# Selectric.net
KiCad netlist of a schematic drawn in EAGLE
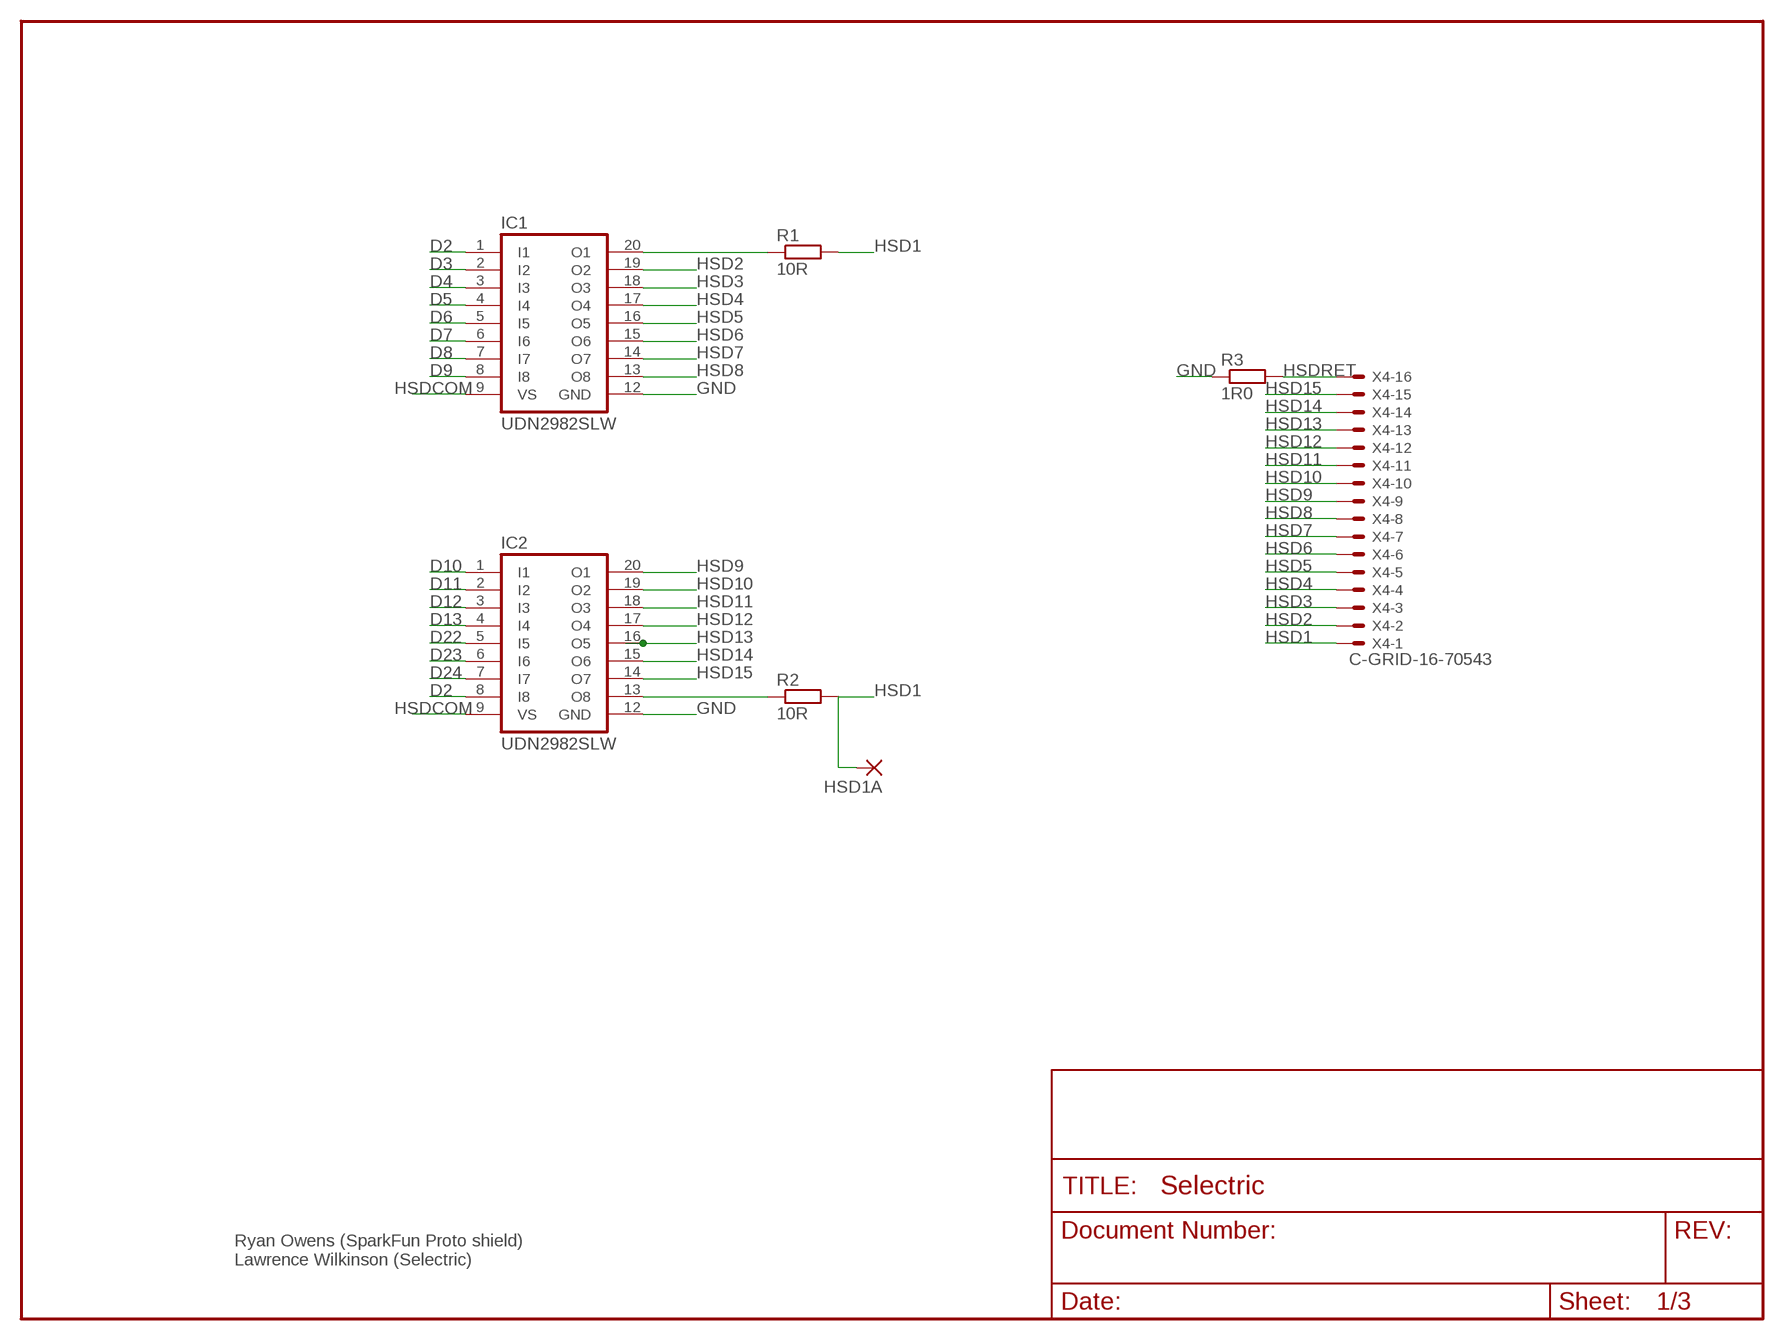
[diagram p0: schematic, sheet 1]
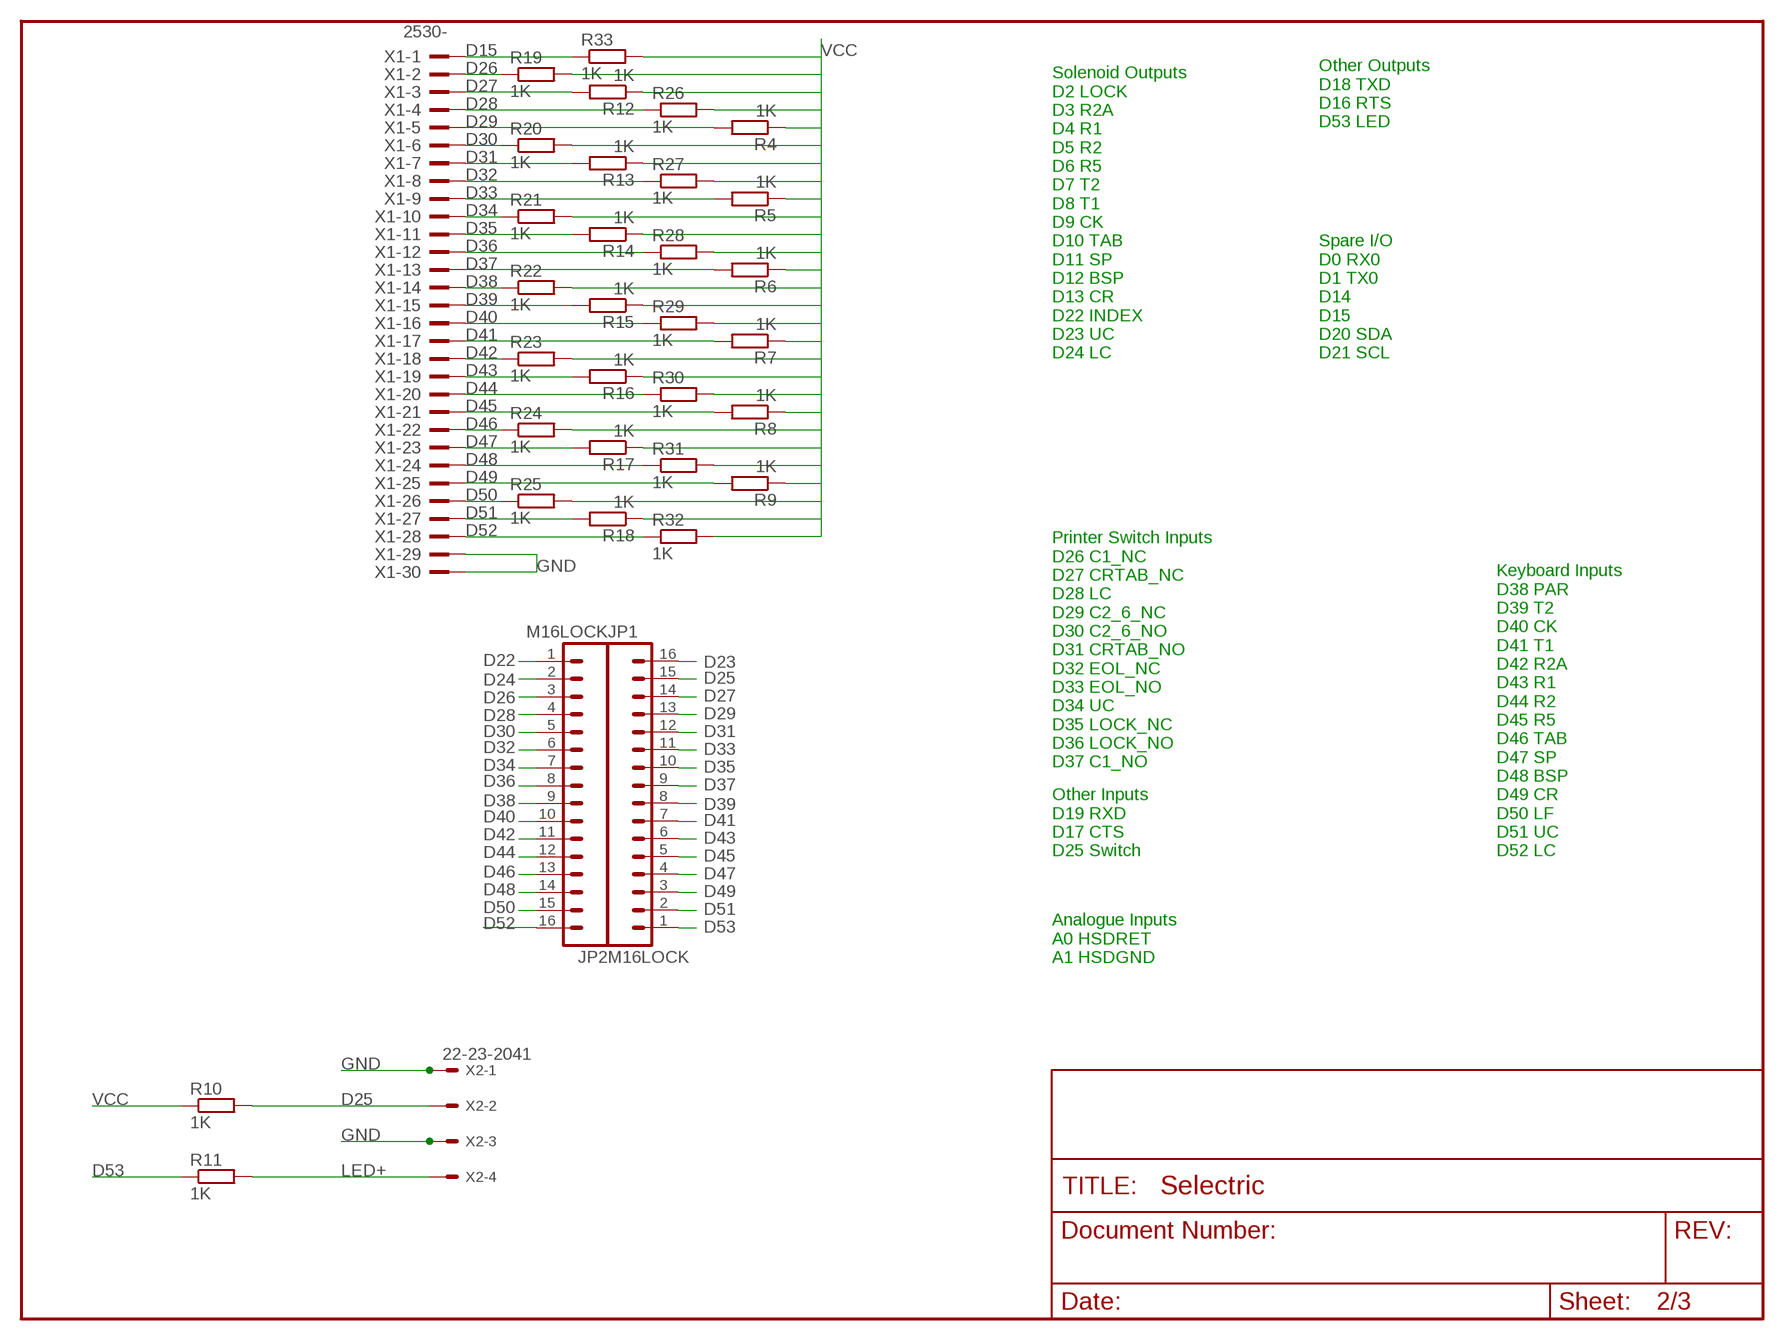
[diagram p1: schematic, sheet 2]
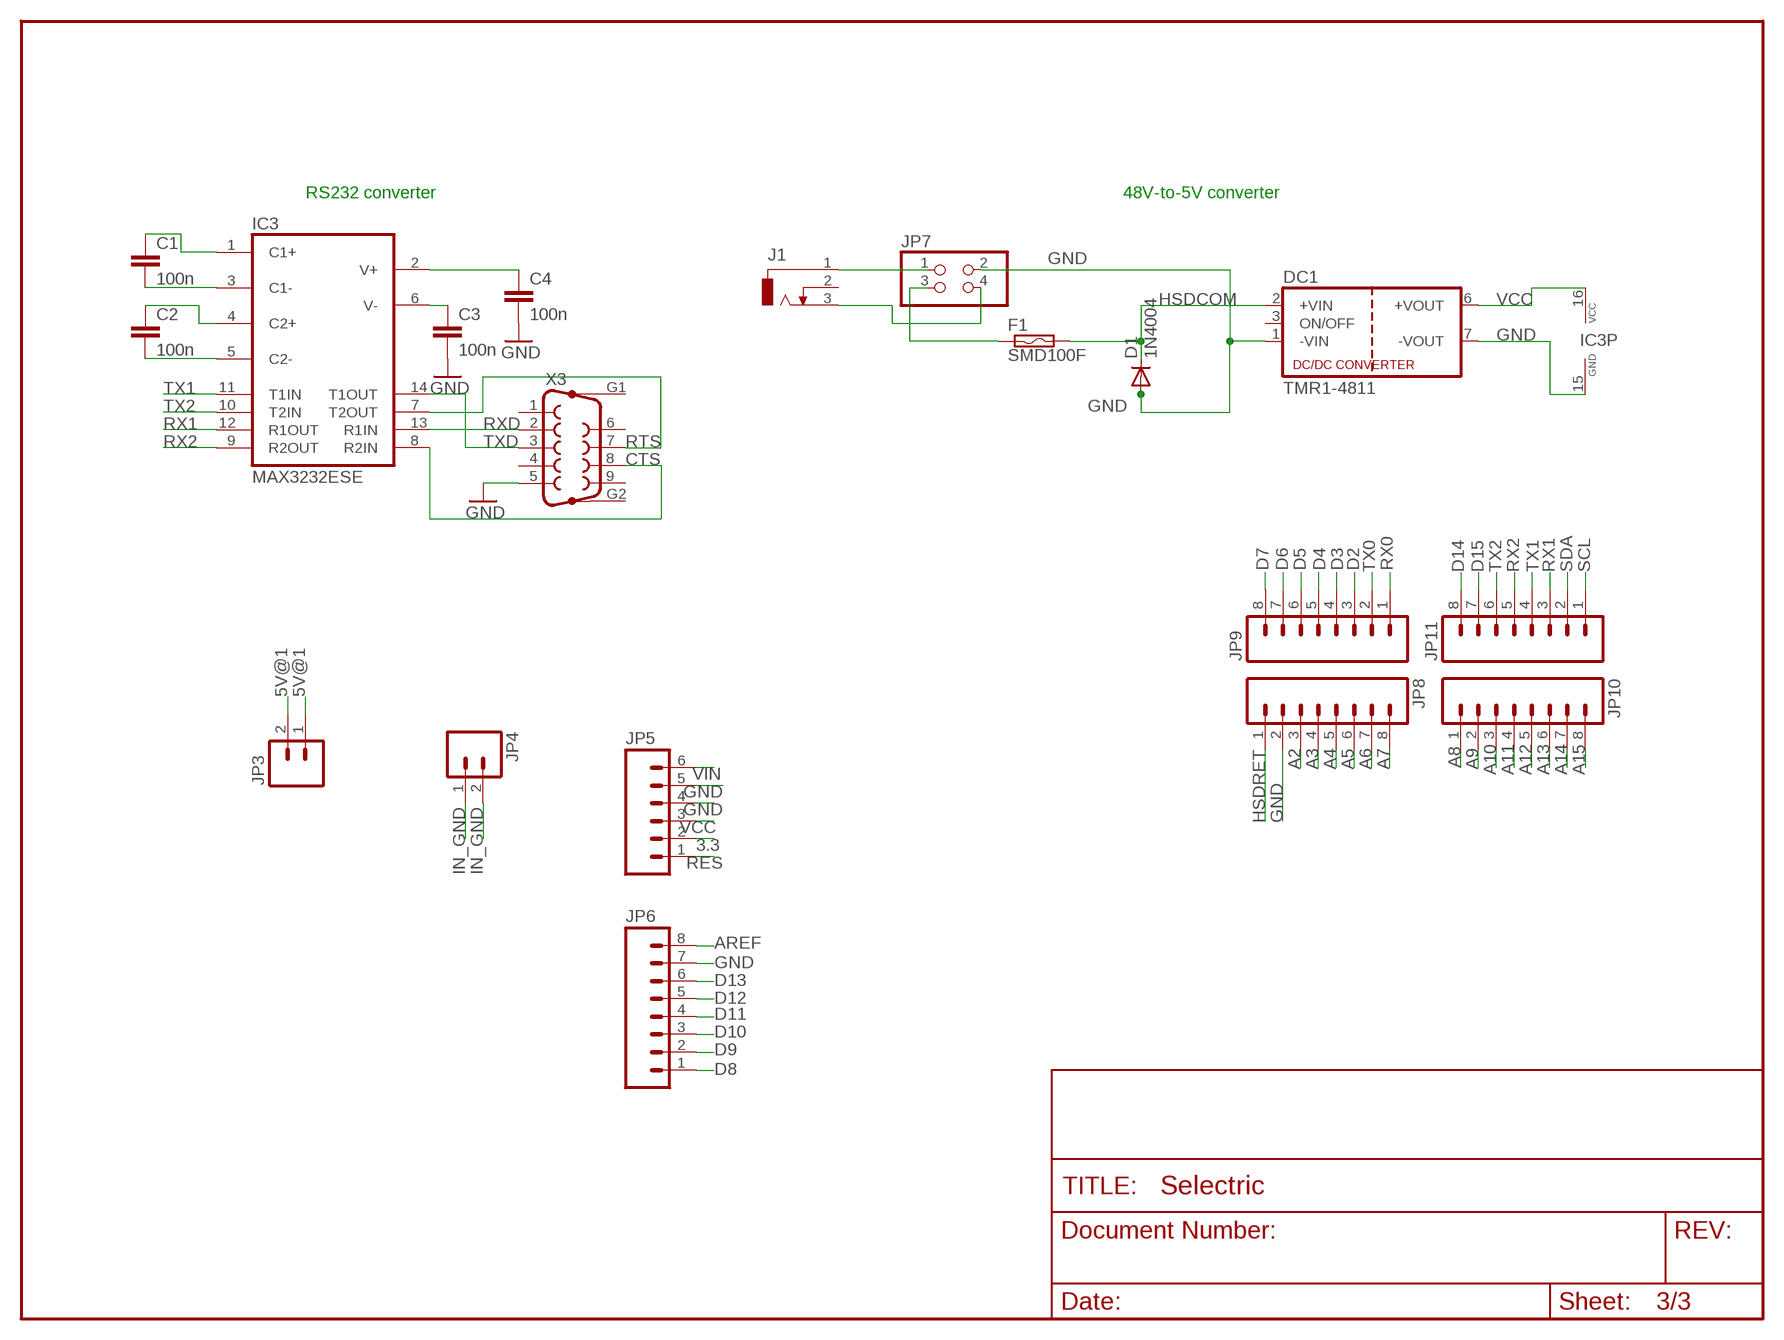
[diagram p2: schematic, sheet 3]

(export (version "E")
  (design (tool "Eeschema 10.0.6"))
  (components
    (comp (ref "HSD1A")
      (value "2,15/1,0")
      (footprint "eagle-import:2,15_1,0")
      (libsource (lib "eagle-import") (part "2,15/1,0"))
    )
    (comp (ref "IC1")
      (value "UDN2982SLW")
      (footprint "eagle-import:SO20W")
      (fields (field (name "MF") "Allegro"))
      (libsource (lib "eagle-import") (part "UDN298SLW2"))
    )
    (comp (ref "IC2")
      (value "UDN2982SLW")
      (footprint "eagle-import:SO20W")
      (fields (field (name "MF") "Allegro"))
      (libsource (lib "eagle-import") (part "UDN298SLW2"))
    )
    (comp (ref "R1")
      (value "10R")
      (footprint "eagle-import:M1206")
      (libsource (lib "eagle-import") (part "R-EU_M1206"))
    )
    (comp (ref "R2")
      (value "10R")
      (footprint "eagle-import:M1206")
      (libsource (lib "eagle-import") (part "R-EU_M1206"))
    )
    (comp (ref "R3")
      (value "1R0")
      (footprint "eagle-import:0922_22")
      (libsource (lib "eagle-import") (part "R-EU_0922/22"))
    )
    (comp (ref "X4")
      (value "C-GRID-16-70543")
      (footprint "eagle-import:70543-16")
      (libsource (lib "eagle-import") (part "C-GRID-16-70543"))
    )
    (comp (ref "JP1")
      (value "M16LOCK")
      (footprint "eagle-import:1X16_LOCK")
      (fields (field (name "MF") "WURTH") (field (name "MPN") "61301611121"))
      (libsource (lib "eagle-import") (part "M16LOCK"))
    )
    (comp (ref "JP2")
      (value "M16LOCK")
      (footprint "eagle-import:1X16_LOCK")
      (fields (field (name "MF") "WURTH") (field (name "MPN") "61301611121"))
      (libsource (lib "eagle-import") (part "M16LOCK"))
    )
    (comp (ref "R4")
      (value "1K")
      (footprint "eagle-import:M1206")
      (libsource (lib "eagle-import") (part "R-EU_M1206"))
    )
    (comp (ref "R5")
      (value "1K")
      (footprint "eagle-import:M1206")
      (libsource (lib "eagle-import") (part "R-EU_M1206"))
    )
    (comp (ref "R6")
      (value "1K")
      (footprint "eagle-import:M1206")
      (libsource (lib "eagle-import") (part "R-EU_M1206"))
    )
    (comp (ref "R7")
      (value "1K")
      (footprint "eagle-import:M1206")
      (libsource (lib "eagle-import") (part "R-EU_M1206"))
    )
    (comp (ref "R8")
      (value "1K")
      (footprint "eagle-import:M1206")
      (libsource (lib "eagle-import") (part "R-EU_M1206"))
    )
    (comp (ref "R9")
      (value "1K")
      (footprint "eagle-import:M1206")
      (libsource (lib "eagle-import") (part "R-EU_M1206"))
    )
    (comp (ref "R10")
      (value "1K")
      (footprint "eagle-import:M1206")
      (libsource (lib "eagle-import") (part "R-EU_M1206"))
    )
    (comp (ref "R11")
      (value "1K")
      (footprint "eagle-import:M1206")
      (libsource (lib "eagle-import") (part "R-EU_M1206"))
    )
    (comp (ref "R12")
      (value "1K")
      (footprint "eagle-import:M1206")
      (libsource (lib "eagle-import") (part "R-EU_M1206"))
    )
    (comp (ref "R13")
      (value "1K")
      (footprint "eagle-import:M1206")
      (libsource (lib "eagle-import") (part "R-EU_M1206"))
    )
    (comp (ref "R14")
      (value "1K")
      (footprint "eagle-import:M1206")
      (libsource (lib "eagle-import") (part "R-EU_M1206"))
    )
    (comp (ref "R15")
      (value "1K")
      (footprint "eagle-import:M1206")
      (libsource (lib "eagle-import") (part "R-EU_M1206"))
    )
    (comp (ref "R16")
      (value "1K")
      (footprint "eagle-import:M1206")
      (libsource (lib "eagle-import") (part "R-EU_M1206"))
    )
    (comp (ref "R17")
      (value "1K")
      (footprint "eagle-import:M1206")
      (libsource (lib "eagle-import") (part "R-EU_M1206"))
    )
    (comp (ref "R18")
      (value "1K")
      (footprint "eagle-import:M1206")
      (libsource (lib "eagle-import") (part "R-EU_M1206"))
    )
    (comp (ref "R19")
      (value "1K")
      (footprint "eagle-import:M1206")
      (libsource (lib "eagle-import") (part "R-EU_M1206"))
    )
    (comp (ref "R20")
      (value "1K")
      (footprint "eagle-import:M1206")
      (libsource (lib "eagle-import") (part "R-EU_M1206"))
    )
    (comp (ref "R21")
      (value "1K")
      (footprint "eagle-import:M1206")
      (libsource (lib "eagle-import") (part "R-EU_M1206"))
    )
    (comp (ref "R22")
      (value "1K")
      (footprint "eagle-import:M1206")
      (libsource (lib "eagle-import") (part "R-EU_M1206"))
    )
    (comp (ref "R23")
      (value "1K")
      (footprint "eagle-import:M1206")
      (libsource (lib "eagle-import") (part "R-EU_M1206"))
    )
    (comp (ref "R24")
      (value "1K")
      (footprint "eagle-import:M1206")
      (libsource (lib "eagle-import") (part "R-EU_M1206"))
    )
    (comp (ref "R25")
      (value "1K")
      (footprint "eagle-import:M1206")
      (libsource (lib "eagle-import") (part "R-EU_M1206"))
    )
    (comp (ref "R26")
      (value "1K")
      (footprint "eagle-import:M1206")
      (libsource (lib "eagle-import") (part "R-EU_M1206"))
    )
    (comp (ref "R27")
      (value "1K")
      (footprint "eagle-import:M1206")
      (libsource (lib "eagle-import") (part "R-EU_M1206"))
    )
    (comp (ref "R28")
      (value "1K")
      (footprint "eagle-import:M1206")
      (libsource (lib "eagle-import") (part "R-EU_M1206"))
    )
    (comp (ref "R29")
      (value "1K")
      (footprint "eagle-import:M1206")
      (libsource (lib "eagle-import") (part "R-EU_M1206"))
    )
    (comp (ref "R30")
      (value "1K")
      (footprint "eagle-import:M1206")
      (libsource (lib "eagle-import") (part "R-EU_M1206"))
    )
    (comp (ref "R31")
      (value "1K")
      (footprint "eagle-import:M1206")
      (libsource (lib "eagle-import") (part "R-EU_M1206"))
    )
    (comp (ref "R32")
      (value "1K")
      (footprint "eagle-import:M1206")
      (libsource (lib "eagle-import") (part "R-EU_M1206"))
    )
    (comp (ref "R33")
      (value "1K")
      (footprint "eagle-import:M1206")
      (libsource (lib "eagle-import") (part "R-EU_M1206"))
    )
    (comp (ref "X1")
      (value "2530-")
      (footprint "eagle-import:PAK100_2500-30")
      (fields (field (name "MF") "3M") (field (name "MPN") "PAK100/2500-30"))
      (libsource (lib "eagle-import") (part "2530-"))
    )
    (comp (ref "X2")
      (value "22-23-2041")
      (footprint "eagle-import:22-23-2041")
      (fields
        (field (name "MF") "MOLEX")
        (field (name "MF_1") "TE CONNECTIVITY")
        (field (name "MPN") "280371-2")
      )
      (libsource (lib "eagle-import") (part "22-23-2041"))
    )
    (comp (ref "C1")
      (value "100n")
      (footprint "eagle-import:C0603")
      (libsource (lib "eagle-import") (part "C-EUC0603"))
    )
    (comp (ref "C2")
      (value "100n")
      (footprint "eagle-import:C0603")
      (libsource (lib "eagle-import") (part "C-EUC0603"))
    )
    (comp (ref "C3")
      (value "100n")
      (footprint "eagle-import:C0603")
      (libsource (lib "eagle-import") (part "C-EUC0603"))
    )
    (comp (ref "C4")
      (value "100n")
      (footprint "eagle-import:C0603")
      (libsource (lib "eagle-import") (part "C-EUC0603"))
    )
    (comp (ref "D1")
      (value "1N4004")
      (footprint "eagle-import:DO41-10")
      (libsource (lib "eagle-import") (part "1N4004"))
    )
    (comp (ref "DC1")
      (value "TMR1-4811")
      (footprint "eagle-import:TRACO_SIP-8")
      (fields (field (name "MF") "TRACO"))
      (libsource (lib "eagle-import") (part "TMR1-4811"))
    )
    (comp (ref "F1")
      (value "SMD100F")
      (footprint "eagle-import:SMD050F")
      (fields (field (name "MF") "Schurter") (field (name "MPN") "3404.0009.11"))
      (libsource (lib "eagle-import") (part "SMDF100"))
    )
    (comp (ref "IC3")
      (value "MAX3232ESE")
      (footprint "eagle-import:SO16")
      (fields (field (name "MF") "MAXIM") (field (name "MPN") "MAX3232CSE"))
      (libsource (lib "eagle-import") (part "MAX3232SEE"))
    )
    (comp (ref "J1")
      (value "DCJ0303")
      (footprint "eagle-import:DCJ0303")
      (libsource (lib "eagle-import") (part "DCJ0303"))
    )
    (comp (ref "JP3")
      (value "M02LOCK")
      (footprint "eagle-import:1X02_LOCK")
      (libsource (lib "eagle-import") (part "M02LOCK"))
    )
    (comp (ref "JP4")
      (value "M02LOCK")
      (footprint "eagle-import:1X02_LOCK")
      (libsource (lib "eagle-import") (part "M02LOCK"))
    )
    (comp (ref "JP5")
      (value "M06LOCK")
      (footprint "eagle-import:1X06_LOCK")
      (fields (field (name "MF") "TE CONNECTIVITY") (field (name "MPN") "826629-6"))
      (libsource (lib "eagle-import") (part "M06LOCK"))
    )
    (comp (ref "JP6")
      (value "M08LOCK")
      (footprint "eagle-import:1X08_LOCK")
      (fields (field (name "MF") "TE CONNECTIVITY") (field (name "MPN") "826629-8"))
      (libsource (lib "eagle-import") (part "M08LOCK"))
    )
    (comp (ref "JP7")
      (value "PINHD-2X2")
      (footprint "eagle-import:2X02")
      (fields (field (name "MF") "TE CONNECTIVITY") (field (name "MPN") "826632-2"))
      (libsource (lib "eagle-import") (part "PINHD-2X2"))
    )
    (comp (ref "JP8")
      (value "M08LOCK")
      (footprint "eagle-import:1X08_LOCK")
      (fields (field (name "MF") "TE CONNECTIVITY") (field (name "MPN") "826629-8"))
      (libsource (lib "eagle-import") (part "M08LOCK"))
    )
    (comp (ref "JP9")
      (value "M08LOCK")
      (footprint "eagle-import:1X08_LOCK")
      (fields (field (name "MF") "TE CONNECTIVITY") (field (name "MPN") "826629-8"))
      (libsource (lib "eagle-import") (part "M08LOCK"))
    )
    (comp (ref "JP10")
      (value "M08LOCK")
      (footprint "eagle-import:1X08_LOCK")
      (fields (field (name "MF") "TE CONNECTIVITY") (field (name "MPN") "826629-8"))
      (libsource (lib "eagle-import") (part "M08LOCK"))
    )
    (comp (ref "JP11")
      (value "M08LOCK")
      (footprint "eagle-import:1X08_LOCK")
      (fields (field (name "MF") "TE CONNECTIVITY") (field (name "MPN") "826629-8"))
      (libsource (lib "eagle-import") (part "M08LOCK"))
    )
    (comp (ref "X3")
      (value "F09HP")
      (footprint "eagle-import:F09HP")
      (fields (field (name "MF") "Amphenol") (field (name "MPN") "FCE17-E09PA-490"))
      (libsource (lib "eagle-import") (part "F09HP"))
    )
  )
  (nets
    (net (code "1") (name "3.3") (class "Default")
      (node (ref "JP5") (pin "2") (pinfunction "2_2") (pintype "passive"))
    )
    (net (code "2") (name "5V@1") (class "Default")
      (node (ref "JP3") (pin "1") (pinfunction "1_1") (pintype "passive"))
      (node (ref "JP3") (pin "2") (pinfunction "2_2") (pintype "passive"))
    )
    (net (code "3") (name "A2") (class "Default")
      (node (ref "JP8") (pin "3") (pinfunction "3_3") (pintype "passive"))
    )
    (net (code "4") (name "A3") (class "Default")
      (node (ref "JP8") (pin "4") (pinfunction "4_4") (pintype "passive"))
    )
    (net (code "5") (name "A4") (class "Default")
      (node (ref "JP8") (pin "5") (pinfunction "5_5") (pintype "passive"))
    )
    (net (code "6") (name "A5") (class "Default")
      (node (ref "JP8") (pin "6") (pinfunction "6_6") (pintype "passive"))
    )
    (net (code "7") (name "A6") (class "Default")
      (node (ref "JP8") (pin "7") (pinfunction "7_7") (pintype "passive"))
    )
    (net (code "8") (name "A7") (class "Default")
      (node (ref "JP8") (pin "8") (pinfunction "8_8") (pintype "passive"))
    )
    (net (code "9") (name "A8") (class "Default")
      (node (ref "JP10") (pin "1") (pinfunction "1_1") (pintype "passive"))
    )
    (net (code "10") (name "A9") (class "Default")
      (node (ref "JP10") (pin "2") (pinfunction "2_2") (pintype "passive"))
    )
    (net (code "11") (name "A10") (class "Default")
      (node (ref "JP10") (pin "3") (pinfunction "3_3") (pintype "passive"))
    )
    (net (code "12") (name "A11") (class "Default")
      (node (ref "JP10") (pin "4") (pinfunction "4_4") (pintype "passive"))
    )
    (net (code "13") (name "A12") (class "Default")
      (node (ref "JP10") (pin "5") (pinfunction "5_5") (pintype "passive"))
    )
    (net (code "14") (name "A13") (class "Default")
      (node (ref "JP10") (pin "6") (pinfunction "6_6") (pintype "passive"))
    )
    (net (code "15") (name "A14") (class "Default")
      (node (ref "JP10") (pin "7") (pinfunction "7_7") (pintype "passive"))
    )
    (net (code "16") (name "A15") (class "Default")
      (node (ref "JP10") (pin "8") (pinfunction "8_8") (pintype "passive"))
    )
    (net (code "17") (name "AREF") (class "Default")
      (node (ref "JP6") (pin "8") (pinfunction "8_8") (pintype "passive"))
    )
    (net (code "18") (name "CTS") (class "Default")
      (node (ref "IC3") (pin "8") (pinfunction "R2IN_8") (pintype "input"))
      (node (ref "X3") (pin "8") (pinfunction "8_8") (pintype "passive"))
    )
    (net (code "19") (name "D2") (class "Default")
      (node (ref "IC1") (pin "1") (pinfunction "I1_1") (pintype "input"))
      (node (ref "IC2") (pin "8") (pinfunction "I8_8") (pintype "input"))
      (node (ref "JP9") (pin "3") (pinfunction "3_3") (pintype "passive"))
    )
    (net (code "20") (name "D3") (class "Default")
      (node (ref "IC1") (pin "2") (pinfunction "I2_2") (pintype "input"))
      (node (ref "JP9") (pin "4") (pinfunction "4_4") (pintype "passive"))
    )
    (net (code "21") (name "D4") (class "Default")
      (node (ref "IC1") (pin "3") (pinfunction "I3_3") (pintype "input"))
      (node (ref "JP9") (pin "5") (pinfunction "5_5") (pintype "passive"))
    )
    (net (code "22") (name "D5") (class "Default")
      (node (ref "IC1") (pin "4") (pinfunction "I4_4") (pintype "input"))
      (node (ref "JP9") (pin "6") (pinfunction "6_6") (pintype "passive"))
    )
    (net (code "23") (name "D6") (class "Default")
      (node (ref "IC1") (pin "5") (pinfunction "I5_5") (pintype "input"))
      (node (ref "JP9") (pin "7") (pinfunction "7_7") (pintype "passive"))
    )
    (net (code "24") (name "D7") (class "Default")
      (node (ref "IC1") (pin "6") (pinfunction "I6_6") (pintype "input"))
      (node (ref "JP9") (pin "8") (pinfunction "8_8") (pintype "passive"))
    )
    (net (code "25") (name "D8") (class "Default")
      (node (ref "IC1") (pin "7") (pinfunction "I7_7") (pintype "input"))
      (node (ref "JP6") (pin "1") (pinfunction "1_1") (pintype "passive"))
    )
    (net (code "26") (name "D9") (class "Default")
      (node (ref "IC1") (pin "8") (pinfunction "I8_8") (pintype "input"))
      (node (ref "JP6") (pin "2") (pinfunction "2_2") (pintype "passive"))
    )
    (net (code "27") (name "D10") (class "Default")
      (node (ref "IC2") (pin "1") (pinfunction "I1_1") (pintype "input"))
      (node (ref "JP6") (pin "3") (pinfunction "3_3") (pintype "passive"))
    )
    (net (code "28") (name "D11") (class "Default")
      (node (ref "IC2") (pin "2") (pinfunction "I2_2") (pintype "input"))
      (node (ref "JP6") (pin "4") (pinfunction "4_4") (pintype "passive"))
    )
    (net (code "29") (name "D12") (class "Default")
      (node (ref "IC2") (pin "3") (pinfunction "I3_3") (pintype "input"))
      (node (ref "JP6") (pin "5") (pinfunction "5_5") (pintype "passive"))
    )
    (net (code "30") (name "D13") (class "Default")
      (node (ref "IC2") (pin "4") (pinfunction "I4_4") (pintype "input"))
      (node (ref "JP6") (pin "6") (pinfunction "6_6") (pintype "passive"))
    )
    (net (code "31") (name "D14") (class "Default")
      (node (ref "JP11") (pin "8") (pinfunction "8_8") (pintype "passive"))
    )
    (net (code "32") (name "D15") (class "Default")
      (node (ref "JP11") (pin "7") (pinfunction "7_7") (pintype "passive"))
      (node (ref "R33") (pin "1") (pinfunction "1_1") (pintype "passive"))
      (node (ref "X1") (pin "1") (pinfunction "KL_1") (pintype "passive"))
    )
    (net (code "33") (name "D22") (class "Default")
      (node (ref "IC2") (pin "5") (pinfunction "I5_5") (pintype "input"))
      (node (ref "JP2") (pin "1") (pinfunction "1_1") (pintype "passive"))
    )
    (net (code "34") (name "D23") (class "Default")
      (node (ref "IC2") (pin "6") (pinfunction "I6_6") (pintype "input"))
      (node (ref "JP1") (pin "16") (pinfunction "16_16") (pintype "passive"))
    )
    (net (code "35") (name "D24") (class "Default")
      (node (ref "IC2") (pin "7") (pinfunction "I7_7") (pintype "input"))
      (node (ref "JP2") (pin "2") (pinfunction "2_2") (pintype "passive"))
    )
    (net (code "36") (name "D25") (class "Default")
      (node (ref "JP1") (pin "15") (pinfunction "15_15") (pintype "passive"))
      (node (ref "R10") (pin "2") (pinfunction "2_2") (pintype "passive"))
      (node (ref "X2") (pin "2") (pinfunction "S_2") (pintype "passive"))
    )
    (net (code "37") (name "D26") (class "Default")
      (node (ref "JP2") (pin "3") (pinfunction "3_3") (pintype "passive"))
      (node (ref "R19") (pin "1") (pinfunction "1_1") (pintype "passive"))
      (node (ref "X1") (pin "2") (pinfunction "KL_2") (pintype "passive"))
    )
    (net (code "38") (name "D27") (class "Default")
      (node (ref "JP1") (pin "14") (pinfunction "14_14") (pintype "passive"))
      (node (ref "R12") (pin "2") (pinfunction "2_2") (pintype "passive"))
      (node (ref "X1") (pin "3") (pinfunction "KL_3") (pintype "passive"))
    )
    (net (code "39") (name "D28") (class "Default")
      (node (ref "JP2") (pin "4") (pinfunction "4_4") (pintype "passive"))
      (node (ref "R26") (pin "1") (pinfunction "1_1") (pintype "passive"))
      (node (ref "X1") (pin "4") (pinfunction "KL_4") (pintype "passive"))
    )
    (net (code "40") (name "D29") (class "Default")
      (node (ref "JP1") (pin "13") (pinfunction "13_13") (pintype "passive"))
      (node (ref "R4") (pin "2") (pinfunction "2_2") (pintype "passive"))
      (node (ref "X1") (pin "5") (pinfunction "KL_5") (pintype "passive"))
    )
    (net (code "41") (name "D30") (class "Default")
      (node (ref "JP2") (pin "5") (pinfunction "5_5") (pintype "passive"))
      (node (ref "R20") (pin "1") (pinfunction "1_1") (pintype "passive"))
      (node (ref "X1") (pin "6") (pinfunction "KL_6") (pintype "passive"))
    )
    (net (code "42") (name "D31") (class "Default")
      (node (ref "JP1") (pin "12") (pinfunction "12_12") (pintype "passive"))
      (node (ref "R13") (pin "2") (pinfunction "2_2") (pintype "passive"))
      (node (ref "X1") (pin "7") (pinfunction "KL_7") (pintype "passive"))
    )
    (net (code "43") (name "D32") (class "Default")
      (node (ref "JP2") (pin "6") (pinfunction "6_6") (pintype "passive"))
      (node (ref "R27") (pin "1") (pinfunction "1_1") (pintype "passive"))
      (node (ref "X1") (pin "8") (pinfunction "KL_8") (pintype "passive"))
    )
    (net (code "44") (name "D33") (class "Default")
      (node (ref "JP1") (pin "11") (pinfunction "11_11") (pintype "passive"))
      (node (ref "R5") (pin "2") (pinfunction "2_2") (pintype "passive"))
      (node (ref "X1") (pin "9") (pinfunction "KL_9") (pintype "passive"))
    )
    (net (code "45") (name "D34") (class "Default")
      (node (ref "JP2") (pin "7") (pinfunction "7_7") (pintype "passive"))
      (node (ref "R21") (pin "1") (pinfunction "1_1") (pintype "passive"))
      (node (ref "X1") (pin "10") (pinfunction "KL_10") (pintype "passive"))
    )
    (net (code "46") (name "D35") (class "Default")
      (node (ref "JP1") (pin "10") (pinfunction "10_10") (pintype "passive"))
      (node (ref "R14") (pin "2") (pinfunction "2_2") (pintype "passive"))
      (node (ref "X1") (pin "11") (pinfunction "KL_11") (pintype "passive"))
    )
    (net (code "47") (name "D36") (class "Default")
      (node (ref "JP2") (pin "8") (pinfunction "8_8") (pintype "passive"))
      (node (ref "R28") (pin "1") (pinfunction "1_1") (pintype "passive"))
      (node (ref "X1") (pin "12") (pinfunction "KL_12") (pintype "passive"))
    )
    (net (code "48") (name "D37") (class "Default")
      (node (ref "JP1") (pin "9") (pinfunction "9_9") (pintype "passive"))
      (node (ref "R6") (pin "2") (pinfunction "2_2") (pintype "passive"))
      (node (ref "X1") (pin "13") (pinfunction "KL_13") (pintype "passive"))
    )
    (net (code "49") (name "D38") (class "Default")
      (node (ref "JP2") (pin "9") (pinfunction "9_9") (pintype "passive"))
      (node (ref "R22") (pin "1") (pinfunction "1_1") (pintype "passive"))
      (node (ref "X1") (pin "14") (pinfunction "KL_14") (pintype "passive"))
    )
    (net (code "50") (name "D39") (class "Default")
      (node (ref "JP1") (pin "8") (pinfunction "8_8") (pintype "passive"))
      (node (ref "R15") (pin "2") (pinfunction "2_2") (pintype "passive"))
      (node (ref "X1") (pin "15") (pinfunction "KL_15") (pintype "passive"))
    )
    (net (code "51") (name "D40") (class "Default")
      (node (ref "JP2") (pin "10") (pinfunction "10_10") (pintype "passive"))
      (node (ref "R29") (pin "1") (pinfunction "1_1") (pintype "passive"))
      (node (ref "X1") (pin "16") (pinfunction "KL_16") (pintype "passive"))
    )
    (net (code "52") (name "D41") (class "Default")
      (node (ref "JP1") (pin "7") (pinfunction "7_7") (pintype "passive"))
      (node (ref "R7") (pin "2") (pinfunction "2_2") (pintype "passive"))
      (node (ref "X1") (pin "17") (pinfunction "KL_17") (pintype "passive"))
    )
    (net (code "53") (name "D42") (class "Default")
      (node (ref "JP2") (pin "11") (pinfunction "11_11") (pintype "passive"))
      (node (ref "R23") (pin "1") (pinfunction "1_1") (pintype "passive"))
      (node (ref "X1") (pin "18") (pinfunction "KL_18") (pintype "passive"))
    )
    (net (code "54") (name "D43") (class "Default")
      (node (ref "JP1") (pin "6") (pinfunction "6_6") (pintype "passive"))
      (node (ref "R16") (pin "2") (pinfunction "2_2") (pintype "passive"))
      (node (ref "X1") (pin "19") (pinfunction "KL_19") (pintype "passive"))
    )
    (net (code "55") (name "D44") (class "Default")
      (node (ref "JP2") (pin "12") (pinfunction "12_12") (pintype "passive"))
      (node (ref "R30") (pin "1") (pinfunction "1_1") (pintype "passive"))
      (node (ref "X1") (pin "20") (pinfunction "KL_20") (pintype "passive"))
    )
    (net (code "56") (name "D45") (class "Default")
      (node (ref "JP1") (pin "5") (pinfunction "5_5") (pintype "passive"))
      (node (ref "R8") (pin "2") (pinfunction "2_2") (pintype "passive"))
      (node (ref "X1") (pin "21") (pinfunction "KL_21") (pintype "passive"))
    )
    (net (code "57") (name "D46") (class "Default")
      (node (ref "JP2") (pin "13") (pinfunction "13_13") (pintype "passive"))
      (node (ref "R24") (pin "1") (pinfunction "1_1") (pintype "passive"))
      (node (ref "X1") (pin "22") (pinfunction "KL_22") (pintype "passive"))
    )
    (net (code "58") (name "D47") (class "Default")
      (node (ref "JP1") (pin "4") (pinfunction "4_4") (pintype "passive"))
      (node (ref "R17") (pin "2") (pinfunction "2_2") (pintype "passive"))
      (node (ref "X1") (pin "23") (pinfunction "KL_23") (pintype "passive"))
    )
    (net (code "59") (name "D48") (class "Default")
      (node (ref "JP2") (pin "14") (pinfunction "14_14") (pintype "passive"))
      (node (ref "R31") (pin "1") (pinfunction "1_1") (pintype "passive"))
      (node (ref "X1") (pin "24") (pinfunction "KL_24") (pintype "passive"))
    )
    (net (code "60") (name "D49") (class "Default")
      (node (ref "JP1") (pin "3") (pinfunction "3_3") (pintype "passive"))
      (node (ref "R9") (pin "2") (pinfunction "2_2") (pintype "passive"))
      (node (ref "X1") (pin "25") (pinfunction "KL_25") (pintype "passive"))
    )
    (net (code "61") (name "D50") (class "Default")
      (node (ref "JP2") (pin "15") (pinfunction "15_15") (pintype "passive"))
      (node (ref "R25") (pin "1") (pinfunction "1_1") (pintype "passive"))
      (node (ref "X1") (pin "26") (pinfunction "KL_26") (pintype "passive"))
    )
    (net (code "62") (name "D51") (class "Default")
      (node (ref "JP1") (pin "2") (pinfunction "2_2") (pintype "passive"))
      (node (ref "R18") (pin "2") (pinfunction "2_2") (pintype "passive"))
      (node (ref "X1") (pin "27") (pinfunction "KL_27") (pintype "passive"))
    )
    (net (code "63") (name "D52") (class "Default")
      (node (ref "JP2") (pin "16") (pinfunction "16_16") (pintype "passive"))
      (node (ref "R32") (pin "1") (pinfunction "1_1") (pintype "passive"))
      (node (ref "X1") (pin "28") (pinfunction "KL_28") (pintype "passive"))
    )
    (net (code "64") (name "D53") (class "Default")
      (node (ref "JP1") (pin "1") (pinfunction "1_1") (pintype "passive"))
      (node (ref "R11") (pin "1") (pinfunction "1_1") (pintype "passive"))
    )
    (net (code "65") (name "GND") (class "Default")
      (node (ref "C3") (pin "2") (pinfunction "2_2") (pintype "passive"))
      (node (ref "C4") (pin "2") (pinfunction "2_2") (pintype "passive"))
      (node (ref "D1") (pin "A") (pinfunction "A_A") (pintype "passive"))
      (node (ref "DC1") (pin "1") (pinfunction "-VIN_1") (pintype "passive"))
      (node (ref "DC1") (pin "7") (pinfunction "-VOUT_7") (pintype "passive"))
      (node (ref "IC1") (pin "12") (pinfunction "GND_12") (pintype "power_in"))
      (node (ref "IC2") (pin "12") (pinfunction "GND_12") (pintype "power_in"))
      (node (ref "IC3") (pin "15") (pinfunction "GND_15") (pintype "power_in"))
      (node (ref "JP5") (pin "4") (pinfunction "4_4") (pintype "passive"))
      (node (ref "JP5") (pin "5") (pinfunction "5_5") (pintype "passive"))
      (node (ref "JP6") (pin "7") (pinfunction "7_7") (pintype "passive"))
      (node (ref "JP7") (pin "2") (pinfunction "2_2") (pintype "passive"))
      (node (ref "JP8") (pin "2") (pinfunction "2_2") (pintype "passive"))
      (node (ref "R3") (pin "1") (pinfunction "1_1") (pintype "passive"))
      (node (ref "X1") (pin "29") (pinfunction "KL_29") (pintype "passive"))
      (node (ref "X1") (pin "30") (pinfunction "KL_30") (pintype "passive"))
      (node (ref "X2") (pin "1") (pinfunction "S_1") (pintype "passive"))
      (node (ref "X2") (pin "3") (pinfunction "S_3") (pintype "passive"))
      (node (ref "X3") (pin "5") (pinfunction "5_5") (pintype "passive"))
    )
    (net (code "66") (name "HSD1") (class "Default")
      (node (ref "HSD1A") (pin "1") (pinfunction "P_1") (pintype "passive"))
      (node (ref "R1") (pin "2") (pinfunction "2_2") (pintype "passive"))
      (node (ref "R2") (pin "2") (pinfunction "2_2") (pintype "passive"))
      (node (ref "X4") (pin "1") (pinfunction "S_1") (pintype "passive"))
    )
    (net (code "67") (name "HSD2") (class "Default")
      (node (ref "IC1") (pin "19") (pinfunction "O2_19") (pintype "open_collector"))
      (node (ref "X4") (pin "2") (pinfunction "S_2") (pintype "passive"))
    )
    (net (code "68") (name "HSD3") (class "Default")
      (node (ref "IC1") (pin "18") (pinfunction "O3_18") (pintype "open_collector"))
      (node (ref "X4") (pin "3") (pinfunction "S_3") (pintype "passive"))
    )
    (net (code "69") (name "HSD4") (class "Default")
      (node (ref "IC1") (pin "17") (pinfunction "O4_17") (pintype "open_collector"))
      (node (ref "X4") (pin "4") (pinfunction "S_4") (pintype "passive"))
    )
    (net (code "70") (name "HSD5") (class "Default")
      (node (ref "IC1") (pin "16") (pinfunction "O5_16") (pintype "open_collector"))
      (node (ref "X4") (pin "5") (pinfunction "S_5") (pintype "passive"))
    )
    (net (code "71") (name "HSD6") (class "Default")
      (node (ref "IC1") (pin "15") (pinfunction "O6_15") (pintype "open_collector"))
      (node (ref "X4") (pin "6") (pinfunction "S_6") (pintype "passive"))
    )
    (net (code "72") (name "HSD7") (class "Default")
      (node (ref "IC1") (pin "14") (pinfunction "O7_14") (pintype "open_collector"))
      (node (ref "X4") (pin "7") (pinfunction "S_7") (pintype "passive"))
    )
    (net (code "73") (name "HSD8") (class "Default")
      (node (ref "IC1") (pin "13") (pinfunction "O8_13") (pintype "open_collector"))
      (node (ref "X4") (pin "8") (pinfunction "S_8") (pintype "passive"))
    )
    (net (code "74") (name "HSD9") (class "Default")
      (node (ref "IC2") (pin "20") (pinfunction "O1_20") (pintype "open_collector"))
      (node (ref "X4") (pin "9") (pinfunction "S_9") (pintype "passive"))
    )
    (net (code "75") (name "HSD10") (class "Default")
      (node (ref "IC2") (pin "19") (pinfunction "O2_19") (pintype "open_collector"))
      (node (ref "X4") (pin "10") (pinfunction "S_10") (pintype "passive"))
    )
    (net (code "76") (name "HSD11") (class "Default")
      (node (ref "IC2") (pin "18") (pinfunction "O3_18") (pintype "open_collector"))
      (node (ref "X4") (pin "11") (pinfunction "S_11") (pintype "passive"))
    )
    (net (code "77") (name "HSD12") (class "Default")
      (node (ref "IC2") (pin "17") (pinfunction "O4_17") (pintype "open_collector"))
      (node (ref "X4") (pin "12") (pinfunction "S_12") (pintype "passive"))
    )
    (net (code "78") (name "HSD13") (class "Default")
      (node (ref "IC2") (pin "16") (pinfunction "O5_16") (pintype "open_collector"))
      (node (ref "X4") (pin "13") (pinfunction "S_13") (pintype "passive"))
    )
    (net (code "79") (name "HSD14") (class "Default")
      (node (ref "IC2") (pin "15") (pinfunction "O6_15") (pintype "open_collector"))
      (node (ref "X4") (pin "14") (pinfunction "S_14") (pintype "passive"))
    )
    (net (code "80") (name "HSD15") (class "Default")
      (node (ref "IC2") (pin "14") (pinfunction "O7_14") (pintype "open_collector"))
      (node (ref "X4") (pin "15") (pinfunction "S_15") (pintype "passive"))
    )
    (net (code "81") (name "HSDCOM") (class "Default")
      (node (ref "D1") (pin "C") (pinfunction "C_C") (pintype "passive"))
      (node (ref "DC1") (pin "2") (pinfunction "+VIN_2") (pintype "passive"))
      (node (ref "F1") (pin "2") (pinfunction "2_2") (pintype "passive"))
      (node (ref "IC1") (pin "9") (pinfunction "VS_9") (pintype "passive"))
      (node (ref "IC2") (pin "9") (pinfunction "VS_9") (pintype "passive"))
    )
    (net (code "82") (name "HSDRET") (class "Default")
      (node (ref "JP8") (pin "1") (pinfunction "1_1") (pintype "passive"))
      (node (ref "R3") (pin "2") (pinfunction "2_2") (pintype "passive"))
      (node (ref "X4") (pin "16") (pinfunction "S_16") (pintype "passive"))
    )
    (net (code "83") (name "IN_GND") (class "Default")
      (node (ref "JP4") (pin "1") (pinfunction "1_1") (pintype "passive"))
      (node (ref "JP4") (pin "2") (pinfunction "2_2") (pintype "passive"))
    )
    (net (code "84") (name "LED+") (class "Default")
      (node (ref "R11") (pin "2") (pinfunction "2_2") (pintype "passive"))
      (node (ref "X2") (pin "4") (pinfunction "S_4") (pintype "passive"))
    )
    (net (code "85") (name "Net-(F1-Pad1)") (class "Default")
      (node (ref "F1") (pin "1") (pinfunction "1_1") (pintype "passive"))
      (node (ref "JP7") (pin "3") (pinfunction "3_3") (pintype "passive"))
    )
    (net (code "86") (name "Net-(IC1-O1)") (class "Default")
      (node (ref "IC1") (pin "20") (pinfunction "O1_20") (pintype "open_collector"))
      (node (ref "R1") (pin "1") (pinfunction "1_1") (pintype "passive"))
    )
    (net (code "87") (name "Net-(IC2-O8)") (class "Default")
      (node (ref "IC2") (pin "13") (pinfunction "O8_13") (pintype "open_collector"))
      (node (ref "R2") (pin "1") (pinfunction "1_1") (pintype "passive"))
    )
    (net (code "88") (name "Net-(IC3A-C1+)") (class "Default")
      (node (ref "C1") (pin "1") (pinfunction "1_1") (pintype "passive"))
      (node (ref "IC3") (pin "1") (pinfunction "C1+_1") (pintype "bidirectional"))
    )
    (net (code "89") (name "Net-(IC3A-C1-)") (class "Default")
      (node (ref "C1") (pin "2") (pinfunction "2_2") (pintype "passive"))
      (node (ref "IC3") (pin "3") (pinfunction "C1-_3") (pintype "bidirectional"))
    )
    (net (code "90") (name "Net-(IC3A-C2+)") (class "Default")
      (node (ref "C2") (pin "1") (pinfunction "1_1") (pintype "passive"))
      (node (ref "IC3") (pin "4") (pinfunction "C2+_4") (pintype "bidirectional"))
    )
    (net (code "91") (name "Net-(IC3A-C2-)") (class "Default")
      (node (ref "C2") (pin "2") (pinfunction "2_2") (pintype "passive"))
      (node (ref "IC3") (pin "5") (pinfunction "C2-_5") (pintype "bidirectional"))
    )
    (net (code "92") (name "Net-(IC3A-V+)") (class "Default")
      (node (ref "C4") (pin "1") (pinfunction "1_1") (pintype "passive"))
      (node (ref "IC3") (pin "2") (pinfunction "V+_2") (pintype "bidirectional"))
    )
    (net (code "93") (name "Net-(IC3A-V-)") (class "Default")
      (node (ref "C3") (pin "1") (pinfunction "1_1") (pintype "passive"))
      (node (ref "IC3") (pin "6") (pinfunction "V-_6") (pintype "bidirectional"))
    )
    (net (code "94") (name "Net-(J1-Pad1)") (class "Default")
      (node (ref "J1") (pin "1") (pinfunction "1_1") (pintype "passive"))
      (node (ref "JP7") (pin "1") (pinfunction "1_1") (pintype "passive"))
    )
    (net (code "95") (name "Net-(J1-Pad3)") (class "Default")
      (node (ref "J1") (pin "3") (pinfunction "3_3") (pintype "passive"))
      (node (ref "JP7") (pin "4") (pinfunction "4_4") (pintype "passive"))
    )
    (net (code "96") (name "RES") (class "Default")
      (node (ref "JP5") (pin "1") (pinfunction "1_1") (pintype "passive"))
    )
    (net (code "97") (name "RTS") (class "Default")
      (node (ref "IC3") (pin "7") (pinfunction "T2OUT_7") (pintype "output"))
      (node (ref "X3") (pin "7") (pinfunction "7_7") (pintype "passive"))
    )
    (net (code "98") (name "RX0") (class "Default")
      (node (ref "JP9") (pin "1") (pinfunction "1_1") (pintype "passive"))
    )
    (net (code "99") (name "RX1") (class "Default")
      (node (ref "IC3") (pin "12") (pinfunction "R1OUT_12") (pintype "output"))
      (node (ref "JP11") (pin "3") (pinfunction "3_3") (pintype "passive"))
    )
    (net (code "100") (name "RX2") (class "Default")
      (node (ref "IC3") (pin "9") (pinfunction "R2OUT_9") (pintype "output"))
      (node (ref "JP11") (pin "5") (pinfunction "5_5") (pintype "passive"))
    )
    (net (code "101") (name "RXD") (class "Default")
      (node (ref "IC3") (pin "13") (pinfunction "R1IN_13") (pintype "input"))
      (node (ref "X3") (pin "2") (pinfunction "2_2") (pintype "passive"))
    )
    (net (code "102") (name "SCL") (class "Default")
      (node (ref "JP11") (pin "1") (pinfunction "1_1") (pintype "passive"))
    )
    (net (code "103") (name "SDA") (class "Default")
      (node (ref "JP11") (pin "2") (pinfunction "2_2") (pintype "passive"))
    )
    (net (code "104") (name "TX0") (class "Default")
      (node (ref "JP9") (pin "2") (pinfunction "2_2") (pintype "passive"))
    )
    (net (code "105") (name "TX1") (class "Default")
      (node (ref "IC3") (pin "11") (pinfunction "T1IN_11") (pintype "input"))
      (node (ref "JP11") (pin "4") (pinfunction "4_4") (pintype "passive"))
    )
    (net (code "106") (name "TX2") (class "Default")
      (node (ref "IC3") (pin "10") (pinfunction "T2IN_10") (pintype "input"))
      (node (ref "JP11") (pin "6") (pinfunction "6_6") (pintype "passive"))
    )
    (net (code "107") (name "TXD") (class "Default")
      (node (ref "IC3") (pin "14") (pinfunction "T1OUT_14") (pintype "output"))
      (node (ref "X3") (pin "3") (pinfunction "3_3") (pintype "passive"))
    )
    (net (code "108") (name "VCC") (class "Default")
      (node (ref "DC1") (pin "6") (pinfunction "+VOUT_6") (pintype "passive"))
      (node (ref "IC3") (pin "16") (pinfunction "VCC_16") (pintype "power_in"))
      (node (ref "JP5") (pin "3") (pinfunction "3_3") (pintype "passive"))
      (node (ref "R10") (pin "1") (pinfunction "1_1") (pintype "passive"))
      (node (ref "R12") (pin "1") (pinfunction "1_1") (pintype "passive"))
      (node (ref "R13") (pin "1") (pinfunction "1_1") (pintype "passive"))
      (node (ref "R14") (pin "1") (pinfunction "1_1") (pintype "passive"))
      (node (ref "R15") (pin "1") (pinfunction "1_1") (pintype "passive"))
      (node (ref "R16") (pin "1") (pinfunction "1_1") (pintype "passive"))
      (node (ref "R17") (pin "1") (pinfunction "1_1") (pintype "passive"))
      (node (ref "R18") (pin "1") (pinfunction "1_1") (pintype "passive"))
      (node (ref "R19") (pin "2") (pinfunction "2_2") (pintype "passive"))
      (node (ref "R20") (pin "2") (pinfunction "2_2") (pintype "passive"))
      (node (ref "R21") (pin "2") (pinfunction "2_2") (pintype "passive"))
      (node (ref "R22") (pin "2") (pinfunction "2_2") (pintype "passive"))
      (node (ref "R23") (pin "2") (pinfunction "2_2") (pintype "passive"))
      (node (ref "R24") (pin "2") (pinfunction "2_2") (pintype "passive"))
      (node (ref "R25") (pin "2") (pinfunction "2_2") (pintype "passive"))
      (node (ref "R26") (pin "2") (pinfunction "2_2") (pintype "passive"))
      (node (ref "R27") (pin "2") (pinfunction "2_2") (pintype "passive"))
      (node (ref "R28") (pin "2") (pinfunction "2_2") (pintype "passive"))
      (node (ref "R29") (pin "2") (pinfunction "2_2") (pintype "passive"))
      (node (ref "R30") (pin "2") (pinfunction "2_2") (pintype "passive"))
      (node (ref "R31") (pin "2") (pinfunction "2_2") (pintype "passive"))
      (node (ref "R32") (pin "2") (pinfunction "2_2") (pintype "passive"))
      (node (ref "R33") (pin "2") (pinfunction "2_2") (pintype "passive"))
      (node (ref "R4") (pin "1") (pinfunction "1_1") (pintype "passive"))
      (node (ref "R5") (pin "1") (pinfunction "1_1") (pintype "passive"))
      (node (ref "R6") (pin "1") (pinfunction "1_1") (pintype "passive"))
      (node (ref "R7") (pin "1") (pinfunction "1_1") (pintype "passive"))
      (node (ref "R8") (pin "1") (pinfunction "1_1") (pintype "passive"))
      (node (ref "R9") (pin "1") (pinfunction "1_1") (pintype "passive"))
    )
    (net (code "109") (name "VIN") (class "Default")
      (node (ref "JP5") (pin "6") (pinfunction "6_6") (pintype "passive"))
    )
    (net (code "110") (name "unconnected-(DC1-ON{slash}OFF-Pad3)") (class "Default")
      (node (ref "DC1") (pin "3") (pinfunction "ON/OFF_3") (pintype "passive"))
    )
    (net (code "111") (name "unconnected-(J1-Pad2)") (class "Default")
      (node (ref "J1") (pin "2") (pinfunction "2_2") (pintype "passive"))
    )
    (net (code "112") (name "unconnected-(X3-Pad1)") (class "Default")
      (node (ref "X3") (pin "1") (pinfunction "1_1") (pintype "passive"))
    )
    (net (code "113") (name "unconnected-(X3-Pad4)") (class "Default")
      (node (ref "X3") (pin "4") (pinfunction "4_4") (pintype "passive"))
    )
    (net (code "114") (name "unconnected-(X3-Pad6)") (class "Default")
      (node (ref "X3") (pin "6") (pinfunction "6_6") (pintype "passive"))
    )
    (net (code "115") (name "unconnected-(X3-Pad9)") (class "Default")
      (node (ref "X3") (pin "9") (pinfunction "9_9") (pintype "passive"))
    )
    (net (code "116") (name "unconnected-(X3-PadG1)") (class "Default")
      (node (ref "X3") (pin "G1") (pinfunction "G1_G1") (pintype "passive"))
    )
    (net (code "117") (name "unconnected-(X3-PadG2)") (class "Default")
      (node (ref "X3") (pin "G2") (pinfunction "G2_G2") (pintype "passive"))
    )
  )
)
